# ARM_LP5951_1_3.net
KiCad netlist of a schematic drawn in Altium Designer
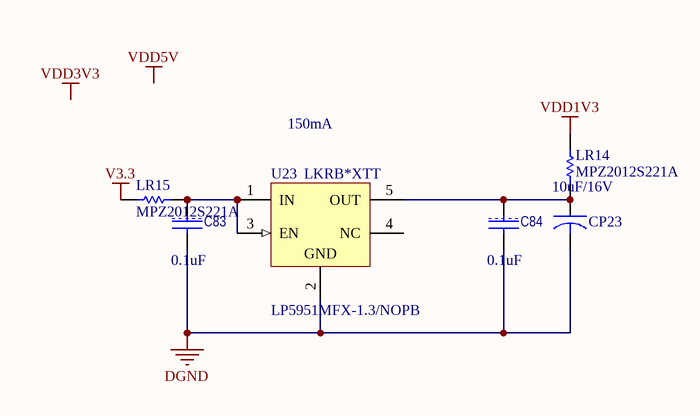
[diagram p0: 电源ARM_LP5951_1.3.SchDoc]

(export (version "E")
  (design (tool "Eeschema 10.0.6"))
  (components
    (comp (ref "C83")
      (value "0.1uF")
      (footprint "1608[0603]C")
      (description "多层陶瓷电容器MLCC - SMD/SMT 0603 0.1uF 50volts X7R 10%")
      (fields (field (name "MANUFACTURER") "TDK") (field (name "MANUFACTURER PART NUMBER") "C1608X7R1H104K"))
      (libsource (lib "*") (part "CAP"))
    )
    (comp (ref "C84")
      (value "0.1uF")
      (footprint "1608[0603]C")
      (description "多层陶瓷电容器MLCC - SMD/SMT 0603 0.1uF 50volts X7R 10%")
      (fields (field (name "MANUFACTURER") "TDK") (field (name "MANUFACTURER PART NUMBER") "C1608X7R1H104K"))
      (libsource (lib "*") (part "CAP"))
    )
    (comp (ref "CP23")
      (value "10uF/16V")
      (footprint "3216[1206]CB")
      (description "钽质电容器-固体SMD 16volts 10uF 10%")
      (fields (field (name "MANUFACTURER") "AVX") (field (name "MANUFACTURER PART NUMBER") "TAJA106K016RNJ"))
      (libsource (lib "*") (part "CAPACITOR"))
    )
    (comp (ref "LR14")
      (value "MPZ2012S221A")
      (footprint "2012[0805]")
      (description "电磁干扰滤波珠子、扼流圈和阵列 Ferrite Chip Beads")
      (fields (field (name "MANUFACTURER") "TDK"))
      (libsource (lib "Miscellaneous Devices") (part "Res Semi"))
    )
    (comp (ref "LR15")
      (value "MPZ2012S221A")
      (footprint "2012[0805]")
      (description "电磁干扰滤波珠子、扼流圈和阵列 Ferrite Chip Beads")
      (fields (field (name "MANUFACTURER") "TDK"))
      (libsource (lib "Miscellaneous Devices") (part "Res Semi"))
    )
    (comp (ref "U23")
      (value "LP5951MFX-1.3/NOPB")
      (footprint "MF05A_N")
      (description "Micropower, 150mA Low-Dropout CMOS Voltage Regulator, 5-pin SOT-23, Pb-Free")
      (fields
        (field (name "PACKAGETOPMARKING") "LKRB*XTT")
        (field (name "MANUFACTURER") "National Semiconductor")
        (field (name "PUBLISHER") "Altium Limited")
      )
      (libsource (lib "NSC LDO") (part "LP5951MFX-1.3/NOPB"))
    )
  )
  (nets
    (net (code "1") (name "DGND") (class "Default")
      (node (ref "C83") (pin "2") (pinfunction "2_2") (pintype "passive"))
      (node (ref "C84") (pin "2") (pinfunction "2_2") (pintype "passive"))
      (node (ref "CP23") (pin "2") (pinfunction "2_2") (pintype "passive"))
      (node (ref "U23") (pin "2") (pinfunction "GND_2") (pintype "power_in"))
    )
    (net (code "2") (name "Net-(U23-EN)") (class "Default")
      (node (ref "C83") (pin "1") (pinfunction "1_1") (pintype "passive"))
      (node (ref "LR15") (pin "1") (pinfunction "1_1") (pintype "passive"))
      (node (ref "U23") (pin "1") (pinfunction "IN_1") (pintype "power_in"))
      (node (ref "U23") (pin "3") (pinfunction "EN_3") (pintype "input"))
    )
    (net (code "3") (name "Net-(U23-OUT)") (class "Default")
      (node (ref "C84") (pin "1") (pinfunction "1_1") (pintype "passive"))
      (node (ref "CP23") (pin "1") (pinfunction "1_1") (pintype "passive"))
      (node (ref "LR14") (pin "1") (pinfunction "1_1") (pintype "passive"))
      (node (ref "U23") (pin "5") (pinfunction "OUT_5") (pintype "power_in"))
    )
    (net (code "4") (name "V3.3") (class "Default")
      (node (ref "LR15") (pin "2") (pinfunction "2_2") (pintype "passive"))
    )
    (net (code "5") (name "VDD1V3") (class "Default")
      (node (ref "LR14") (pin "2") (pinfunction "2_2") (pintype "passive"))
    )
    (net (code "8") (name "unconnected-(U23-NC-Pad4)") (class "Default")
      (node (ref "U23") (pin "4") (pinfunction "NC_4") (pintype "passive"))
    )
  )
)
